# 4_Sensors.net
KiCad netlist of a schematic drawn in Altium Designer
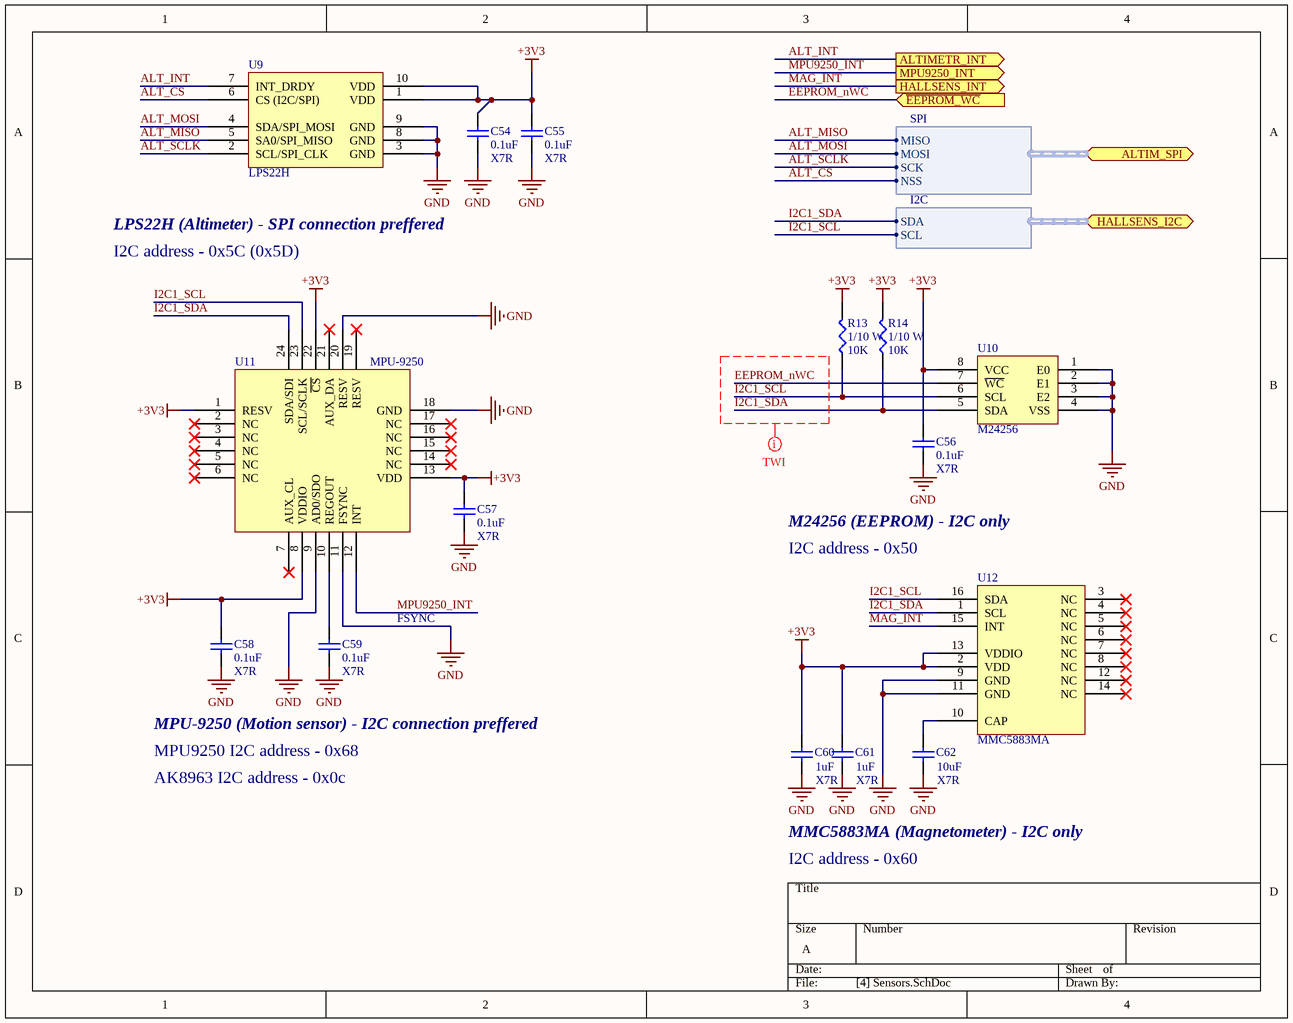
[diagram p0: [4] Sensors.SchDoc]

(export (version "E")
  (design (tool "Eeschema 10.0.6"))
  (components
    (comp (ref "C54")
      (value "0.1uF")
      (footprint "CAP0402")
      (description "Surface-mount ceramic multilayer capacitor")
      (fields (field (name "VOLTAGE") "100V") (field (name "TOLERANCE") "10%") (field (name "TYPE") "X7R"))
      (libsource (lib "Capacitors") (part "ChipCap 0.1uF X7R"))
    )
    (comp (ref "C55")
      (value "0.1uF")
      (footprint "CAP0402")
      (description "Surface-mount ceramic multilayer capacitor")
      (fields (field (name "VOLTAGE") "100V") (field (name "TOLERANCE") "10%") (field (name "TYPE") "X7R"))
      (libsource (lib "Capacitors") (part "ChipCap 0.1uF X7R"))
    )
    (comp (ref "C56")
      (value "0.1uF")
      (footprint "CAP0603")
      (description "Surface-mount ceramic multilayer capacitor")
      (fields (field (name "VOLTAGE") "100V") (field (name "TOLERANCE") "10%") (field (name "TYPE") "X7R"))
      (libsource (lib "Capacitors") (part "ChipCap 0.1uF X7R"))
    )
    (comp (ref "C57")
      (value "0.1uF")
      (footprint "CAP0603")
      (description "Surface-mount ceramic multilayer capacitor")
      (fields (field (name "VOLTAGE") "100V") (field (name "TOLERANCE") "10%") (field (name "TYPE") "X7R"))
      (libsource (lib "Capacitors") (part "ChipCap 0.1uF X7R"))
    )
    (comp (ref "C58")
      (value "0.1uF")
      (footprint "CAP0603")
      (description "Surface-mount ceramic multilayer capacitor")
      (fields (field (name "VOLTAGE") "100V") (field (name "TOLERANCE") "10%") (field (name "TYPE") "X7R"))
      (libsource (lib "Capacitors") (part "ChipCap 0.1uF X7R"))
    )
    (comp (ref "C59")
      (value "0.1uF")
      (footprint "CAP0603")
      (description "Surface-mount ceramic multilayer capacitor")
      (fields (field (name "VOLTAGE") "100V") (field (name "TOLERANCE") "10%") (field (name "TYPE") "X7R"))
      (libsource (lib "Capacitors") (part "ChipCap 0.1uF X7R"))
    )
    (comp (ref "C60")
      (value "1uF")
      (footprint "CAP0603")
      (description "Surface-mount ceramic multilayer capacitor")
      (fields (field (name "VOLTAGE") "25V") (field (name "TOLERANCE") "10%") (field (name "TYPE") "X7R"))
      (libsource (lib "Capacitors") (part "ChipCap 1uF X7R"))
    )
    (comp (ref "C61")
      (value "1uF")
      (footprint "CAP0603")
      (description "Surface-mount ceramic multilayer capacitor")
      (fields (field (name "VOLTAGE") "25V") (field (name "TOLERANCE") "10%") (field (name "TYPE") "X7R"))
      (libsource (lib "Capacitors") (part "ChipCap 1uF X7R"))
    )
    (comp (ref "C62")
      (value "10uF")
      (footprint "CAP0805")
      (description "Surface-mount ceramic multilayer capacitor")
      (fields (field (name "VOLTAGE") "25V") (field (name "TOLERANCE") "10%") (field (name "TYPE") "X7R"))
      (libsource (lib "Capacitors") (part "ChipCap 10uF X7R"))
    )
    (comp (ref "R13")
      (value "10K")
      (footprint "RES0805")
      (description "Think Film Chip resistor")
      (fields
        (field (name "TOLERANCE") "1%")
        (field (name "RATING") "1/10 W")
        (field (name "Comment") "ChipRes 10K 1%")
      )
      (libsource (lib "Resistors") (part "ChipRes 10K 1%"))
    )
    (comp (ref "R14")
      (value "10K")
      (footprint "RES0805")
      (description "Think Film Chip resistor")
      (fields
        (field (name "TOLERANCE") "1%")
        (field (name "RATING") "1/10 W")
        (field (name "Comment") "ChipRes 10K 1%")
      )
      (libsource (lib "Resistors") (part "ChipRes 10K 1%"))
    )
    (comp (ref "U9")
      (value "LPS22H")
      (footprint "HLGA-10L")
      (description "MEMS nano pressure sensor: 260-1260 hPa")
      (libsource (lib "ST Sensors") (part "LPS22H"))
    )
    (comp (ref "U10")
      (value "M24256")
      (footprint "SOIC8")
      (description "256 Kbit I2C EEPROM")
      (libsource (lib "ST EEPROM") (part "M24256"))
    )
    (comp (ref "U11")
      (value "MPU-9250")
      (footprint "InvenSense:QFN24")
      (description "9-Axis sensor")
      (libsource (lib "InvenSense") (part "MPU-9250"))
    )
    (comp (ref "U12")
      (value "MMC5883MA")
      (footprint "LGA16")
      (description "3-axis Magnetic Sensor")
      (libsource (lib "MEMSIC 3-Axis Magnetometer") (part "MMC5883MA"))
    )
  )
  (nets
    (net (code "3") (name "+3V3") (class "Default")
      (node (ref "C54") (pin "2") (pinfunction "2_2") (pintype "passive"))
      (node (ref "C55") (pin "2") (pinfunction "2_2") (pintype "passive"))
      (node (ref "C56") (pin "2") (pinfunction "2_2") (pintype "passive"))
      (node (ref "C57") (pin "2") (pinfunction "2_2") (pintype "passive"))
      (node (ref "C58") (pin "2") (pinfunction "2_2") (pintype "passive"))
      (node (ref "C60") (pin "2") (pinfunction "2_2") (pintype "passive"))
      (node (ref "C61") (pin "2") (pinfunction "2_2") (pintype "passive"))
      (node (ref "R13") (pin "2") (pintype "passive"))
      (node (ref "R14") (pin "2") (pintype "passive"))
      (node (ref "U10") (pin "8") (pinfunction "VCC_8") (pintype "passive"))
      (node (ref "U11") (pin "1") (pinfunction "RESV_1") (pintype "passive"))
      (node (ref "U11") (pin "13") (pinfunction "VDD_13") (pintype "passive"))
      (node (ref "U11") (pin "22") (pinfunction "~{CS}_22") (pintype "passive"))
      (node (ref "U11") (pin "8") (pinfunction "VDDIO_8") (pintype "passive"))
      (node (ref "U12") (pin "13") (pinfunction "VDDIO_13") (pintype "passive"))
      (node (ref "U12") (pin "2") (pinfunction "VDD_2") (pintype "passive"))
      (node (ref "U9") (pin "1") (pinfunction "VDD_1") (pintype "passive"))
      (node (ref "U9") (pin "10") (pinfunction "VDD_10") (pintype "passive"))
    )
    (net (code "4") (name "/ALT_CS") (class "Default")
      (node (ref "U9") (pin "6") (pinfunction "CS_(I2C/SPI)_6") (pintype "passive"))
    )
    (net (code "5") (name "/ALT_INT") (class "Default")
      (node (ref "U9") (pin "7") (pinfunction "INT_DRDY_7") (pintype "passive"))
    )
    (net (code "6") (name "/ALT_MISO") (class "Default")
      (node (ref "U9") (pin "5") (pinfunction "SA0/SPI_MISO_5") (pintype "passive"))
    )
    (net (code "7") (name "/ALT_MOSI") (class "Default")
      (node (ref "U9") (pin "4") (pinfunction "SDA/SPI_MOSI_4") (pintype "passive"))
    )
    (net (code "8") (name "/ALT_SCLK") (class "Default")
      (node (ref "U9") (pin "2") (pinfunction "SCL/SPI_CLK_2") (pintype "passive"))
    )
    (net (code "9") (name "/EEPROM_nWC") (class "Default")
      (node (ref "U10") (pin "7") (pinfunction "~{WC}_7") (pintype "passive"))
    )
    (net (code "10") (name "/I2C1_SCL") (class "Default")
      (node (ref "R13") (pin "1") (pintype "passive"))
      (node (ref "U10") (pin "6") (pinfunction "SCL_6") (pintype "passive"))
      (node (ref "U11") (pin "23") (pinfunction "SCL/SCLK_23") (pintype "passive"))
      (node (ref "U12") (pin "16") (pinfunction "SDA_16") (pintype "passive"))
    )
    (net (code "11") (name "/I2C1_SDA") (class "Default")
      (node (ref "R14") (pin "1") (pintype "passive"))
      (node (ref "U10") (pin "5") (pinfunction "SDA_5") (pintype "passive"))
      (node (ref "U11") (pin "24") (pinfunction "SDA/SDI_24") (pintype "passive"))
      (node (ref "U12") (pin "1") (pinfunction "SCL_1") (pintype "passive"))
    )
    (net (code "12") (name "/MAG_INT") (class "Default")
      (node (ref "U12") (pin "15") (pinfunction "INT_15") (pintype "passive"))
    )
    (net (code "13") (name "/MPU9250_INT") (class "Default")
      (node (ref "U11") (pin "12") (pinfunction "INT_12") (pintype "passive"))
    )
    (net (code "16") (name "GND") (class "Default")
      (node (ref "C54") (pin "1") (pinfunction "1_1") (pintype "passive"))
      (node (ref "C55") (pin "1") (pinfunction "1_1") (pintype "passive"))
      (node (ref "C56") (pin "1") (pinfunction "1_1") (pintype "passive"))
      (node (ref "C57") (pin "1") (pinfunction "1_1") (pintype "passive"))
      (node (ref "C58") (pin "1") (pinfunction "1_1") (pintype "passive"))
      (node (ref "C59") (pin "1") (pinfunction "1_1") (pintype "passive"))
      (node (ref "C60") (pin "1") (pinfunction "1_1") (pintype "passive"))
      (node (ref "C61") (pin "1") (pinfunction "1_1") (pintype "passive"))
      (node (ref "C62") (pin "1") (pinfunction "1_1") (pintype "passive"))
      (node (ref "U10") (pin "1") (pinfunction "E0_1") (pintype "passive"))
      (node (ref "U10") (pin "2") (pinfunction "E1_2") (pintype "passive"))
      (node (ref "U10") (pin "3") (pinfunction "E2_3") (pintype "passive"))
      (node (ref "U10") (pin "4") (pinfunction "VSS_4") (pintype "passive"))
      (node (ref "U11") (pin "11") (pinfunction "FSYNC_11") (pintype "passive"))
      (node (ref "U11") (pin "18") (pinfunction "GND_18") (pintype "passive"))
      (node (ref "U11") (pin "20") (pinfunction "RESV_20") (pintype "passive"))
      (node (ref "U11") (pin "9") (pinfunction "AD0/SDO_9") (pintype "passive"))
      (node (ref "U12") (pin "11") (pinfunction "GND_11") (pintype "passive"))
      (node (ref "U12") (pin "9") (pinfunction "GND_9") (pintype "passive"))
      (node (ref "U9") (pin "3") (pinfunction "GND_3") (pintype "passive"))
      (node (ref "U9") (pin "8") (pinfunction "GND_8") (pintype "passive"))
      (node (ref "U9") (pin "9") (pinfunction "GND_9") (pintype "passive"))
    )
    (net (code "17") (name "Net-(U11-REGOUT)") (class "Default")
      (node (ref "C59") (pin "2") (pinfunction "2_2") (pintype "passive"))
      (node (ref "U11") (pin "10") (pinfunction "REGOUT_10") (pintype "passive"))
    )
    (net (code "18") (name "Net-(U12-CAP)") (class "Default")
      (node (ref "C62") (pin "2") (pinfunction "2_2") (pintype "passive"))
      (node (ref "U12") (pin "10") (pinfunction "CAP_10") (pintype "passive"))
    )
    (net (code "19") (name "unconnected-(U11-AUX_CL-Pad7)") (class "Default")
      (node (ref "U11") (pin "7") (pinfunction "AUX_CL_7") (pintype "passive+no_connect"))
    )
    (net (code "20") (name "unconnected-(U11-AUX_DA-Pad21)") (class "Default")
      (node (ref "U11") (pin "21") (pinfunction "AUX_DA_21") (pintype "passive+no_connect"))
    )
    (net (code "21") (name "unconnected-(U11-NC-Pad2)") (class "Default")
      (node (ref "U11") (pin "2") (pinfunction "NC_2") (pintype "passive+no_connect"))
    )
    (net (code "22") (name "unconnected-(U11-NC-Pad3)") (class "Default")
      (node (ref "U11") (pin "3") (pinfunction "NC_3") (pintype "passive+no_connect"))
    )
    (net (code "23") (name "unconnected-(U11-NC-Pad4)") (class "Default")
      (node (ref "U11") (pin "4") (pinfunction "NC_4") (pintype "passive+no_connect"))
    )
    (net (code "24") (name "unconnected-(U11-NC-Pad5)") (class "Default")
      (node (ref "U11") (pin "5") (pinfunction "NC_5") (pintype "passive+no_connect"))
    )
    (net (code "25") (name "unconnected-(U11-NC-Pad6)") (class "Default")
      (node (ref "U11") (pin "6") (pinfunction "NC_6") (pintype "passive+no_connect"))
    )
    (net (code "26") (name "unconnected-(U11-NC-Pad14)") (class "Default")
      (node (ref "U11") (pin "14") (pinfunction "NC_14") (pintype "passive+no_connect"))
    )
    (net (code "27") (name "unconnected-(U11-NC-Pad15)") (class "Default")
      (node (ref "U11") (pin "15") (pinfunction "NC_15") (pintype "passive+no_connect"))
    )
    (net (code "28") (name "unconnected-(U11-NC-Pad16)") (class "Default")
      (node (ref "U11") (pin "16") (pinfunction "NC_16") (pintype "passive+no_connect"))
    )
    (net (code "29") (name "unconnected-(U11-NC-Pad17)") (class "Default")
      (node (ref "U11") (pin "17") (pinfunction "NC_17") (pintype "passive+no_connect"))
    )
    (net (code "30") (name "unconnected-(U11-RESV-Pad19)") (class "Default")
      (node (ref "U11") (pin "19") (pinfunction "RESV_19") (pintype "passive+no_connect"))
    )
    (net (code "31") (name "unconnected-(U12-NC-Pad3)") (class "Default")
      (node (ref "U12") (pin "3") (pinfunction "NC_3") (pintype "passive+no_connect"))
    )
    (net (code "32") (name "unconnected-(U12-NC-Pad4)") (class "Default")
      (node (ref "U12") (pin "4") (pinfunction "NC_4") (pintype "passive+no_connect"))
    )
    (net (code "33") (name "unconnected-(U12-NC-Pad5)") (class "Default")
      (node (ref "U12") (pin "5") (pinfunction "NC_5") (pintype "passive+no_connect"))
    )
    (net (code "34") (name "unconnected-(U12-NC-Pad6)") (class "Default")
      (node (ref "U12") (pin "6") (pinfunction "NC_6") (pintype "passive+no_connect"))
    )
    (net (code "35") (name "unconnected-(U12-NC-Pad7)") (class "Default")
      (node (ref "U12") (pin "7") (pinfunction "NC_7") (pintype "passive+no_connect"))
    )
    (net (code "36") (name "unconnected-(U12-NC-Pad8)") (class "Default")
      (node (ref "U12") (pin "8") (pinfunction "NC_8") (pintype "passive+no_connect"))
    )
    (net (code "37") (name "unconnected-(U12-NC-Pad12)") (class "Default")
      (node (ref "U12") (pin "12") (pinfunction "NC_12") (pintype "passive+no_connect"))
    )
    (net (code "38") (name "unconnected-(U12-NC-Pad14)") (class "Default")
      (node (ref "U12") (pin "14") (pinfunction "NC_14") (pintype "passive+no_connect"))
    )
  )
)
